# MCU.net
KiCad netlist of a schematic drawn in Altium Designer
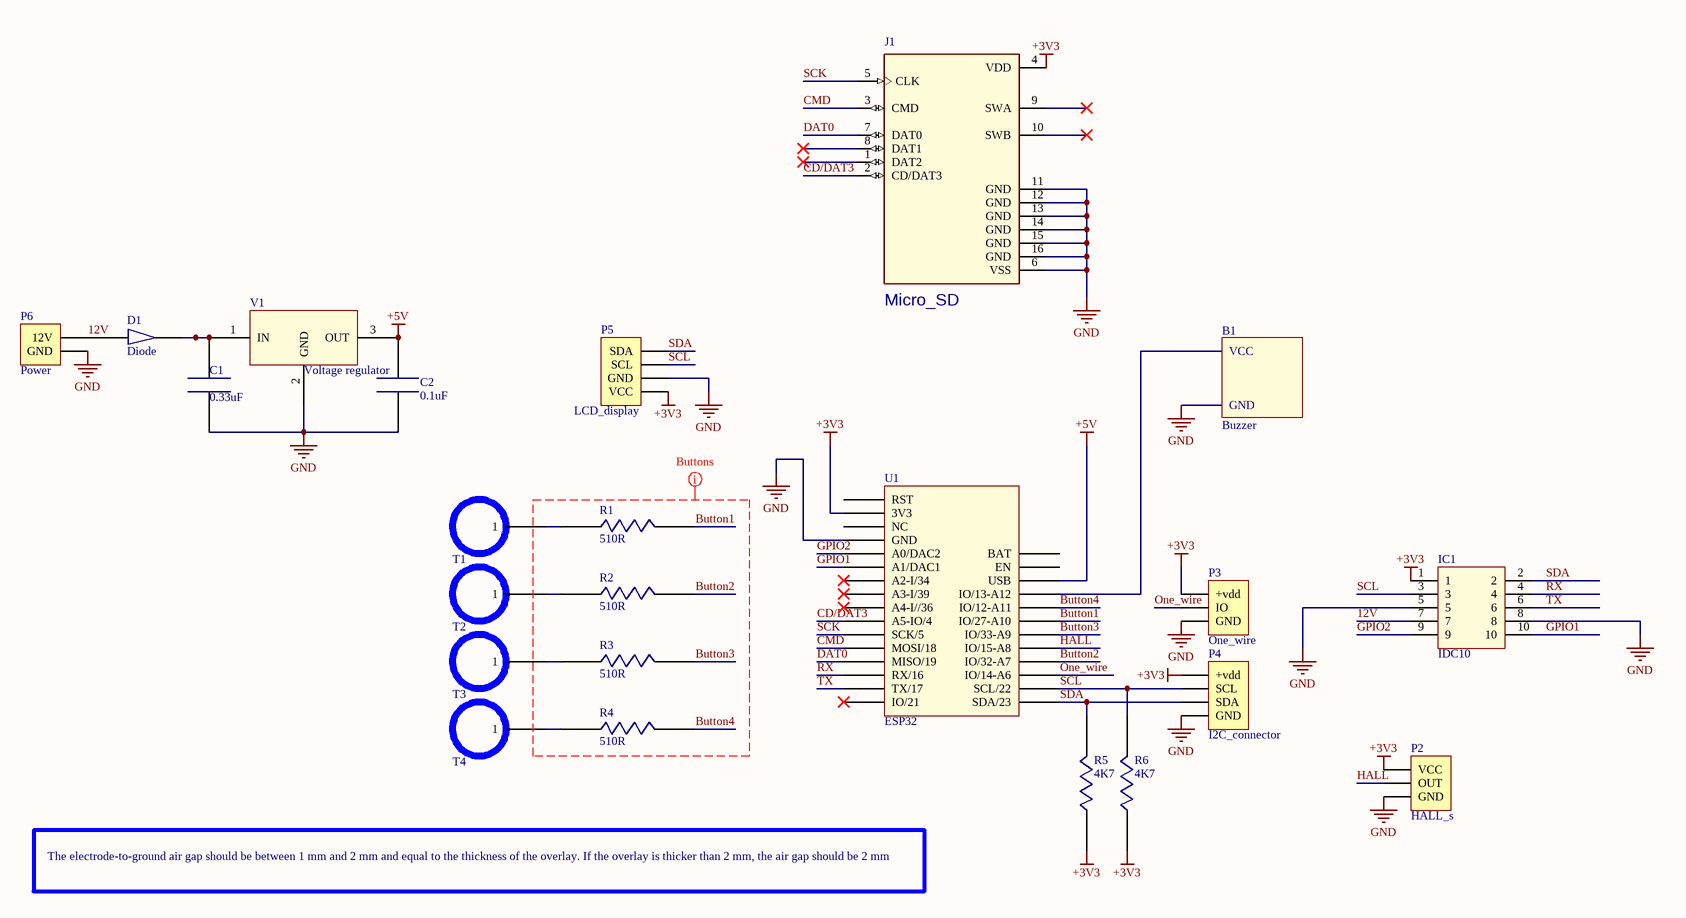
[diagram p0: MCU.SchDoc]

(export (version "E")
  (design (tool "Eeschema 10.0.6"))
  (components
    (comp (ref "B1")
      (value "Buzzer")
      (footprint "Incubator_HUZZAH32:Buzzer")
      (description "MULTICOMP         MCABT-458-RC            SOUNDER, 75DB, 1-25V, SMD")
      (fields
        (field (name "MANUFACTURER") "Multicomp")
        (field (name "MANUFACTURER PART NUMBER") "MCABT-458-RC")
      )
      (libsource (lib "Incubator_HUZZAH32") (part "Buzzer"))
    )
    (comp (ref "C1")
      (value "0.33uF")
      (footprint "Incubator_HUZZAH32:CAP0603")
      (fields
        (field (name "MANUFACTURER") "TDK")
        (field (name "MANUFACTURER PART NUMBER") "C1608X7R1H334K080AC")
        (field (name "PCN PART NUMBER") "MLCC Part Number Change 30/Nov/2012")
      )
      (libsource (lib "Incubator_HUZZAH32") (part "0.33uF"))
    )
    (comp (ref "C2")
      (value "0.1uF")
      (footprint "Incubator_HUZZAH32:CAP0603")
      (description "CAP CER 0.1UF 50V X7R 0603")
      (fields
        (field (name "MANUFACTURER") "Kyocera AVX")
        (field (name "MANUFACTURER PART NUMBER") "06035C104K4Z2A")
      )
      (libsource (lib "Incubator_HUZZAH32") (part "0.1uF"))
    )
    (comp (ref "D1")
      (value "Diode")
      (footprint "Incubator_HUZZAH32:SODFL350X110-2N")
      (description "NXP         PMEG2010ER             Schottky Rectifier, Single, 20 V, 1 A, SOD-123W, 2 Pins, 340 mV")
      (fields
        (field (name "MANUFACTURER") "NXP Semiconductors")
        (field (name "MANUFACTURER PART NUMBER") "PMEG2010ER")
      )
      (libsource (lib "Incubator_HUZZAH32") (part "20V,1A, SOD-123"))
    )
    (comp (ref "IC1")
      (value "IDC10")
      (footprint "Incubator_HUZZAH32:IDC10")
      (description "BOX HEADER 2.54MM MALE STR 10POS")
      (fields
        (field (name "MANUFACTURER") "Wurth Electronics")
        (field (name "MANUFACTURER PART NUMBER") "61201021621")
      )
      (libsource (lib "Incubator_HUZZAH32") (part "IDC10"))
    )
    (comp (ref "J1")
      (value "Micro_SD")
      (footprint "TE_2201778-1")
      (description "MICRO SD PUSH PUSH LOW PROFILE TYPE")
      (fields (field (name "MP") "2201778-1") (field (name "MF") "TE Connectivity"))
      (libsource (lib "2201778-1") (part "2201778-1"))
    )
    (comp (ref "P2")
      (value "HALL_s")
      (footprint "HDR1X3")
      (description "Header, 3-Pin")
      (fields (field (name "PUBLISHER") "Altium Limited"))
      (libsource (lib "Miscellaneous Connectors") (part "Header 3"))
    )
    (comp (ref "P3")
      (value "One_wire")
      (footprint "HDR1X3")
      (description "Header, 3-Pin")
      (fields (field (name "PUBLISHER") "Altium Limited"))
      (libsource (lib "Miscellaneous Connectors") (part "Header 3"))
    )
    (comp (ref "P4")
      (value "I2C_connector")
      (footprint "HDR1X4")
      (description "Header, 4-Pin")
      (fields (field (name "PUBLISHER") "Altium Limited"))
      (libsource (lib "") (part "Header 4_1"))
    )
    (comp (ref "P5")
      (value "LCD_display")
      (footprint "Incubator_HUZZAH32:LCD_display")
      (description "Header, 4-Pin")
      (fields (field (name "PUBLISHER") "Altium Limited"))
      (libsource (lib "Miscellaneous Connectors") (part "Header 4"))
    )
    (comp (ref "P6")
      (value "Power")
      (footprint "HDR1X2")
      (description "Header, 2-Pin")
      (fields (field (name "PUBLISHER") "Altium Limited"))
      (libsource (lib "Miscellaneous Connectors") (part "Header 2"))
    )
    (comp (ref "R1")
      (value "510R")
      (footprint "Incubator_HUZZAH32:RES0603")
      (description "Res Thick Film 0603 510 Ohm 1% 0.1W(1/10W) ±100ppm/C Molded SMD Automotive Punched T/R")
      (fields
        (field (name "MANUFACTURER") "Panasonic")
        (field (name "MANUFACTURER PART NUMBER") "ERJ-3EKF5100V")
      )
      (libsource (lib "Incubator_HUZZAH32") (part "510R"))
    )
    (comp (ref "R2")
      (value "510R")
      (footprint "Incubator_HUZZAH32:RES0603")
      (description "Res Thick Film 0603 510 Ohm 1% 0.1W(1/10W) ±100ppm/C Molded SMD Automotive Punched T/R")
      (fields
        (field (name "MANUFACTURER") "Panasonic")
        (field (name "MANUFACTURER PART NUMBER") "ERJ-3EKF5100V")
      )
      (libsource (lib "Incubator_HUZZAH32") (part "510R"))
    )
    (comp (ref "R3")
      (value "510R")
      (footprint "Incubator_HUZZAH32:RES0603")
      (description "Res Thick Film 0603 510 Ohm 1% 0.1W(1/10W) ±100ppm/C Molded SMD Automotive Punched T/R")
      (fields
        (field (name "MANUFACTURER") "Panasonic")
        (field (name "MANUFACTURER PART NUMBER") "ERJ-3EKF5100V")
      )
      (libsource (lib "Incubator_HUZZAH32") (part "510R"))
    )
    (comp (ref "R4")
      (value "510R")
      (footprint "Incubator_HUZZAH32:RES0603")
      (description "Res Thick Film 0603 510 Ohm 1% 0.1W(1/10W) ±100ppm/C Molded SMD Automotive Punched T/R")
      (fields
        (field (name "MANUFACTURER") "Panasonic")
        (field (name "MANUFACTURER PART NUMBER") "ERJ-3EKF5100V")
      )
      (libsource (lib "Incubator_HUZZAH32") (part "510R"))
    )
    (comp (ref "R5")
      (value "4K7")
      (footprint "Incubator_HUZZAH32:RES0603")
      (description "Res Thick Film 0603 4.7K Ohm 1% 0.1W(1/10W) ±100ppm/C Molded SMD Automotive T/R")
      (fields
        (field (name "MANUFACTURER") "Panasonic")
        (field (name "MANUFACTURER PART NUMBER") "ERJ-3EKF4701V")
      )
      (libsource (lib "Incubator_HUZZAH32") (part "4K7"))
    )
    (comp (ref "R6")
      (value "4K7")
      (footprint "Incubator_HUZZAH32:RES0603")
      (description "Res Thick Film 0603 4.7K Ohm 1% 0.1W(1/10W) ±100ppm/C Molded SMD Automotive T/R")
      (fields
        (field (name "MANUFACTURER") "Panasonic")
        (field (name "MANUFACTURER PART NUMBER") "ERJ-3EKF4701V")
      )
      (libsource (lib "Incubator_HUZZAH32") (part "4K7"))
    )
    (comp (ref "T1")
      (value "Touch button")
      (footprint "Incubator_HUZZAH32:Touch_Button")
      (libsource (lib "Incubator_HUZZAH32") (part "Touch button"))
    )
    (comp (ref "T2")
      (value "Touch button")
      (footprint "Incubator_HUZZAH32:Touch_Button")
      (libsource (lib "Incubator_HUZZAH32") (part "Touch button"))
    )
    (comp (ref "T3")
      (value "Touch button")
      (footprint "Incubator_HUZZAH32:Touch_Button")
      (libsource (lib "Incubator_HUZZAH32") (part "Touch button"))
    )
    (comp (ref "T4")
      (value "Touch button")
      (footprint "Incubator_HUZZAH32:Touch_Button")
      (libsource (lib "Incubator_HUZZAH32") (part "Touch button"))
    )
    (comp (ref "U1")
      (value "ESP32")
      (footprint "Incubator_HUZZAH32:ESP32")
      (description "Dip connectro for MCU")
      (fields
        (field (name "MANUFACTURER") "Adafruit Industries")
        (field (name "MANUFACTURER PART NUMBER") "3405")
      )
      (libsource (lib "Incubator_HUZZAH32") (part "3405"))
    )
    (comp (ref "V1")
      (value "Voltage regulator")
      (footprint "Incubator_HUZZAH32:DPAK248P950X240-3N")
      (fields
        (field (name "MANUFACTURER") "ON Semiconductor / Fairchild")
        (field (name "MANUFACTURER PART NUMBER") "KA7805ERTF")
      )
      (libsource (lib "Incubator_HUZZAH32") (part "5-20V"))
    )
  )
  (nets
    (net (code "1") (name "+3V3") (class "Default")
      (node (ref "IC1") (pin "1") (pinfunction "1_1") (pintype "passive"))
      (node (ref "J1") (pin "4") (pinfunction "VDD_4") (pintype "power_in"))
      (node (ref "P2") (pin "1") (pinfunction "+vdd_1") (pintype "passive"))
      (node (ref "P3") (pin "1") (pinfunction "+vdd_1") (pintype "passive"))
      (node (ref "P4") (pin "1") (pinfunction "+vdd_1") (pintype "passive"))
      (node (ref "P5") (pin "1") (pinfunction "VCC_1") (pintype "passive"))
      (node (ref "R5") (pin "1") (pinfunction "1_1") (pintype "passive"))
      (node (ref "R6") (pin "1") (pinfunction "1_1") (pintype "passive"))
      (node (ref "U1") (pin "2") (pinfunction "3V3_2") (pintype "passive"))
    )
    (net (code "2") (name "+5V") (class "Default")
      (node (ref "C2") (pin "2") (pinfunction "2_2") (pintype "passive"))
      (node (ref "U1") (pin "26") (pinfunction "USB_26") (pintype "passive"))
      (node (ref "V1") (pin "3") (pinfunction "OUT_3") (pintype "passive"))
    )
    (net (code "3") (name "/12V") (class "Default")
      (node (ref "D1") (pin "2") (pinfunction "2_2") (pintype "passive"))
      (node (ref "IC1") (pin "7") (pinfunction "7_7") (pintype "passive"))
      (node (ref "P6") (pin "2") (pinfunction "12V_2") (pintype "passive"))
    )
    (net (code "4") (name "/Button1") (class "Default")
      (node (ref "R1") (pin "2") (pinfunction "2_2") (pintype "passive"))
      (node (ref "U1") (pin "23") (pinfunction "IO/27-A10_23") (pintype "passive"))
    )
    (net (code "5") (name "/Button2") (class "Default")
      (node (ref "R2") (pin "2") (pinfunction "2_2") (pintype "passive"))
      (node (ref "U1") (pin "20") (pinfunction "IO/32-A7_20") (pintype "passive"))
    )
    (net (code "6") (name "/Button3") (class "Default")
      (node (ref "R3") (pin "2") (pinfunction "2_2") (pintype "passive"))
      (node (ref "U1") (pin "22") (pinfunction "IO/33-A9_22") (pintype "passive"))
    )
    (net (code "7") (name "/Button4") (class "Default")
      (node (ref "R4") (pin "2") (pinfunction "2_2") (pintype "passive"))
      (node (ref "U1") (pin "24") (pinfunction "IO/12-A11_24") (pintype "passive"))
    )
    (net (code "8") (name "/CD{slash}DAT3") (class "Default")
      (node (ref "J1") (pin "2") (pinfunction "CD/DAT3_2") (pintype "bidirectional"))
      (node (ref "U1") (pin "10") (pinfunction "A5-IO/4_10") (pintype "passive"))
    )
    (net (code "9") (name "/CMD") (class "Default")
      (node (ref "J1") (pin "3") (pinfunction "CMD_3") (pintype "bidirectional"))
      (node (ref "U1") (pin "12") (pinfunction "MOSI/18_12") (pintype "passive"))
    )
    (net (code "10") (name "/DAT0") (class "Default")
      (node (ref "J1") (pin "7") (pinfunction "DAT0_7") (pintype "bidirectional"))
      (node (ref "U1") (pin "13") (pinfunction "MISO/19_13") (pintype "passive"))
    )
    (net (code "11") (name "/GPIO1") (class "Default")
      (node (ref "IC1") (pin "10") (pinfunction "10_10") (pintype "passive"))
      (node (ref "U1") (pin "6") (pinfunction "A1/DAC1_6") (pintype "passive"))
    )
    (net (code "12") (name "/GPIO2") (class "Default")
      (node (ref "IC1") (pin "9") (pinfunction "9_9") (pintype "passive"))
      (node (ref "U1") (pin "5") (pinfunction "A0/DAC2_5") (pintype "passive"))
    )
    (net (code "13") (name "/HALL") (class "Default")
      (node (ref "P2") (pin "2") (pinfunction "IO_2") (pintype "passive"))
      (node (ref "U1") (pin "21") (pinfunction "IO/15-A8_21") (pintype "passive"))
    )
    (net (code "14") (name "/One_wire") (class "Default")
      (node (ref "P3") (pin "2") (pinfunction "IO_2") (pintype "passive"))
      (node (ref "U1") (pin "19") (pinfunction "IO/14-A6_19") (pintype "passive"))
    )
    (net (code "15") (name "/RX") (class "Default")
      (node (ref "IC1") (pin "4") (pinfunction "4_4") (pintype "passive"))
      (node (ref "U1") (pin "14") (pinfunction "RX/16_14") (pintype "passive"))
    )
    (net (code "16") (name "/SCK") (class "Default")
      (node (ref "J1") (pin "5") (pinfunction "CLK_5") (pintype "input"))
      (node (ref "U1") (pin "11") (pinfunction "SCK/5_11") (pintype "passive"))
    )
    (net (code "17") (name "/SCL") (class "Default")
      (node (ref "IC1") (pin "3") (pinfunction "3_3") (pintype "passive"))
      (node (ref "P4") (pin "2") (pinfunction "SCL_2") (pintype "passive"))
      (node (ref "P5") (pin "3") (pinfunction "SCL_3") (pintype "passive"))
      (node (ref "R6") (pin "2") (pinfunction "2_2") (pintype "passive"))
      (node (ref "U1") (pin "18") (pinfunction "SCL/22_18") (pintype "passive"))
    )
    (net (code "18") (name "/SDA") (class "Default")
      (node (ref "IC1") (pin "2") (pinfunction "2_2") (pintype "passive"))
      (node (ref "P4") (pin "3") (pinfunction "SDA_3") (pintype "passive"))
      (node (ref "P5") (pin "4") (pinfunction "SDA_4") (pintype "passive"))
      (node (ref "R5") (pin "2") (pinfunction "2_2") (pintype "passive"))
      (node (ref "U1") (pin "17") (pinfunction "SDA/23_17") (pintype "passive"))
    )
    (net (code "19") (name "/TX") (class "Default")
      (node (ref "IC1") (pin "6") (pinfunction "6_6") (pintype "passive"))
      (node (ref "U1") (pin "15") (pinfunction "TX/17_15") (pintype "passive"))
    )
    (net (code "20") (name "GND") (class "Default")
      (node (ref "B1") (pin "2") (pinfunction "GND_2") (pintype "passive"))
      (node (ref "C1") (pin "1") (pinfunction "1_1") (pintype "passive"))
      (node (ref "C2") (pin "1") (pinfunction "1_1") (pintype "passive"))
      (node (ref "IC1") (pin "5") (pinfunction "5_5") (pintype "passive"))
      (node (ref "IC1") (pin "8") (pinfunction "8_8") (pintype "passive"))
      (node (ref "J1") (pin "11") (pinfunction "GND_11") (pintype "power_in"))
      (node (ref "J1") (pin "12") (pinfunction "GND_12") (pintype "power_in"))
      (node (ref "J1") (pin "13") (pinfunction "GND_13") (pintype "power_in"))
      (node (ref "J1") (pin "14") (pinfunction "GND_14") (pintype "power_in"))
      (node (ref "J1") (pin "15") (pinfunction "GND_15") (pintype "power_in"))
      (node (ref "J1") (pin "16") (pinfunction "GND_16") (pintype "power_in"))
      (node (ref "J1") (pin "6") (pinfunction "VSS_6") (pintype "power_in"))
      (node (ref "P2") (pin "3") (pinfunction "GND_3") (pintype "passive"))
      (node (ref "P3") (pin "3") (pinfunction "GND_3") (pintype "passive"))
      (node (ref "P4") (pin "4") (pinfunction "GND_4") (pintype "passive"))
      (node (ref "P5") (pin "2") (pinfunction "GND_2") (pintype "passive"))
      (node (ref "P6") (pin "1") (pinfunction "GND_1") (pintype "passive"))
      (node (ref "U1") (pin "4") (pinfunction "GND_4") (pintype "passive"))
      (node (ref "V1") (pin "2") (pinfunction "GND_2") (pintype "passive"))
    )
    (net (code "21") (name "Net-(B1-VCC)") (class "Default")
      (node (ref "B1") (pin "1") (pinfunction "VCC_1") (pintype "passive"))
      (node (ref "U1") (pin "25") (pinfunction "IO/13-A12_25") (pintype "passive"))
    )
    (net (code "22") (name "Net-(R1-Pad1)") (class "Default")
      (node (ref "R1") (pin "1") (pinfunction "1_1") (pintype "passive"))
      (node (ref "T1") (pin "1") (pinfunction "1_1") (pintype "passive"))
    )
    (net (code "23") (name "Net-(R2-Pad1)") (class "Default")
      (node (ref "R2") (pin "1") (pinfunction "1_1") (pintype "passive"))
      (node (ref "T2") (pin "1") (pinfunction "1_1") (pintype "passive"))
    )
    (net (code "24") (name "Net-(R3-Pad1)") (class "Default")
      (node (ref "R3") (pin "1") (pinfunction "1_1") (pintype "passive"))
      (node (ref "T3") (pin "1") (pinfunction "1_1") (pintype "passive"))
    )
    (net (code "25") (name "Net-(R4-Pad1)") (class "Default")
      (node (ref "R4") (pin "1") (pinfunction "1_1") (pintype "passive"))
      (node (ref "T4") (pin "1") (pinfunction "1_1") (pintype "passive"))
    )
    (net (code "26") (name "Net-(V1-IN)") (class "Default")
      (node (ref "C1") (pin "2") (pinfunction "2_2") (pintype "passive"))
      (node (ref "D1") (pin "1") (pinfunction "1_1") (pintype "passive"))
      (node (ref "V1") (pin "1") (pinfunction "IN_1") (pintype "passive"))
    )
    (net (code "27") (name "unconnected-(J1-DAT1-Pad8)") (class "Default")
      (node (ref "J1") (pin "8") (pinfunction "DAT1_8") (pintype "bidirectional+no_connect"))
    )
    (net (code "28") (name "unconnected-(J1-DAT2-Pad1)") (class "Default")
      (node (ref "J1") (pin "1") (pinfunction "DAT2_1") (pintype "bidirectional+no_connect"))
    )
    (net (code "29") (name "unconnected-(J1-SWA-Pad9)") (class "Default")
      (node (ref "J1") (pin "9") (pinfunction "SWA_9") (pintype "passive+no_connect"))
    )
    (net (code "30") (name "unconnected-(J1-SWB-Pad10)") (class "Default")
      (node (ref "J1") (pin "10") (pinfunction "SWB_10") (pintype "passive+no_connect"))
    )
    (net (code "31") (name "unconnected-(U1-A2-I{slash}34-Pad7)") (class "Default")
      (node (ref "U1") (pin "7") (pinfunction "A2-I/34_7") (pintype "passive+no_connect"))
    )
    (net (code "32") (name "unconnected-(U1-A3-I{slash}39-Pad8)") (class "Default")
      (node (ref "U1") (pin "8") (pinfunction "A3-I/39_8") (pintype "passive+no_connect"))
    )
    (net (code "33") (name "unconnected-(U1-A4-I{slash}{slash}36-Pad9)") (class "Default")
      (node (ref "U1") (pin "9") (pinfunction "A4-I//36_9") (pintype "passive+no_connect"))
    )
    (net (code "34") (name "unconnected-(U1-BAT-Pad28)") (class "Default")
      (node (ref "U1") (pin "28") (pinfunction "BAT_28") (pintype "passive"))
    )
    (net (code "35") (name "unconnected-(U1-EN-Pad27)") (class "Default")
      (node (ref "U1") (pin "27") (pinfunction "EN_27") (pintype "passive"))
    )
    (net (code "36") (name "unconnected-(U1-IO{slash}21-Pad16)") (class "Default")
      (node (ref "U1") (pin "16") (pinfunction "IO/21_16") (pintype "passive+no_connect"))
    )
    (net (code "37") (name "unconnected-(U1-NC-Pad3)") (class "Default")
      (node (ref "U1") (pin "3") (pinfunction "NC_3") (pintype "passive"))
    )
    (net (code "38") (name "unconnected-(U1-RST-Pad1)") (class "Default")
      (node (ref "U1") (pin "1") (pinfunction "RST_1") (pintype "passive"))
    )
  )
)
